# Rectfier.net
KiCad netlist of a schematic drawn in Altium Designer
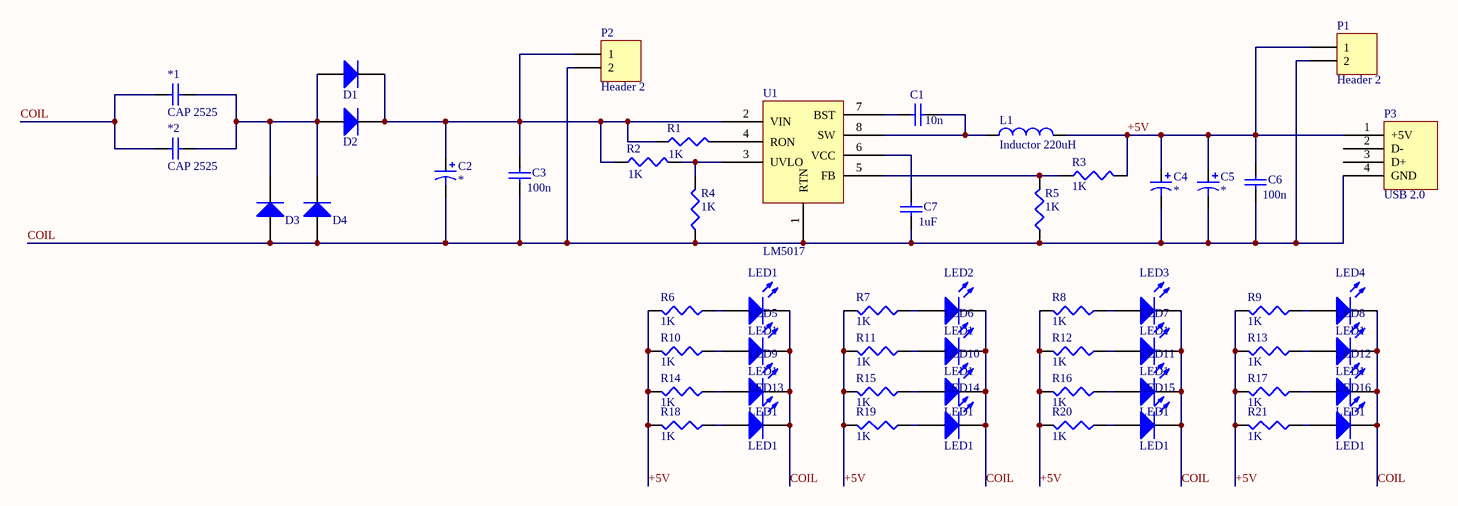
[diagram p0: Rectfier.SchDoc]

(export (version "E")
  (design (tool "Eeschema 10.0.6"))
  (components
    (comp (ref "*1")
      (value "CAP 2525")
      (footprint "CAP 2525")
      (libsource (lib "GaN_Schlib") (part "CAP 2525"))
    )
    (comp (ref "*2")
      (value "CAP 2525")
      (footprint "CAP 2525")
      (libsource (lib "GaN_Schlib") (part "CAP 2525"))
    )
    (comp (ref "C1")
      (value "10n")
      (footprint "0603 IPC Low Density")
      (description "Capacitor (Semiconductor SIM Model)")
      (fields (field (name "Comment") "Cap Semi") (field (name "PUBLISHER") "Altium Limited"))
      (libsource (lib "Miscellaneous Devices") (part "Cap Semi"))
    )
    (comp (ref "C2")
      (value "CAP SMD ELECT")
      (footprint "CAP 200uF")
      (fields (field (name "ALTIUM_VALUE") "*"))
      (libsource (lib "GaN_Schlib") (part "CAP SMD ELECT"))
    )
    (comp (ref "C3")
      (value "100n")
      (footprint "0805 IPC Low Density")
      (description "Capacitor (Semiconductor SIM Model)")
      (fields (field (name "Comment") "Cap Semi") (field (name "PUBLISHER") "Altium Limited"))
      (libsource (lib "Miscellaneous Devices") (part "Cap Semi"))
    )
    (comp (ref "C4")
      (value "CAP SMD ELECT")
      (footprint "CAP 47uF")
      (fields (field (name "ALTIUM_VALUE") "*"))
      (libsource (lib "GaN_Schlib") (part "CAP SMD ELECT"))
    )
    (comp (ref "C5")
      (value "CAP SMD ELECT")
      (footprint "CAP 47uF")
      (fields (field (name "ALTIUM_VALUE") "*"))
      (libsource (lib "GaN_Schlib") (part "CAP SMD ELECT"))
    )
    (comp (ref "C6")
      (value "100n")
      (footprint "1206 IPC Low Density")
      (description "Capacitor (Semiconductor SIM Model)")
      (fields (field (name "Comment") "Cap Semi") (field (name "PUBLISHER") "Altium Limited"))
      (libsource (lib "Miscellaneous Devices") (part "Cap Semi"))
    )
    (comp (ref "C7")
      (value "1uF")
      (footprint "0603 IPC Low Density")
      (description "Capacitor (Semiconductor SIM Model)")
      (fields (field (name "Comment") "Cap Semi") (field (name "PUBLISHER") "Altium Limited"))
      (libsource (lib "Miscellaneous Devices") (part "Cap Semi"))
    )
    (comp (ref "D1")
      (value "SiC Schottky Diode")
      (footprint "TO-263-2")
      (description "Cree Silicon Carbide Schottky Diode")
      (libsource (lib "GaN_Schlib") (part "SiC Schottky Diode"))
    )
    (comp (ref "D2")
      (value "SiC Schottky Diode")
      (footprint "QFN 3.3")
      (description "Cree Silicon Carbide Schottky Diode")
      (libsource (lib "GaN_Schlib") (part "SiC Schottky Diode"))
    )
    (comp (ref "D3")
      (value "SiC Schottky Diode")
      (footprint "QFN 3.3")
      (description "Cree Silicon Carbide Schottky Diode")
      (libsource (lib "GaN_Schlib") (part "SiC Schottky Diode"))
    )
    (comp (ref "D4")
      (value "SiC Schottky Diode")
      (footprint "TO-263-2")
      (description "Cree Silicon Carbide Schottky Diode")
      (libsource (lib "GaN_Schlib") (part "SiC Schottky Diode"))
    )
    (comp (ref "L1")
      (value "Inductor 220uH")
      (footprint "220u Indcutor small")
      (libsource (lib "GaN_Schlib") (part "Inductor 220uH"))
    )
    (comp (ref "LED1") (value "LED1") (footprint "LED 5MM") (libsource (lib "GaN_Schlib") (part "LED1")))
    (comp (ref "LED2") (value "LED1") (footprint "LED 5MM") (libsource (lib "GaN_Schlib") (part "LED1")))
    (comp (ref "LED3") (value "LED1") (footprint "LED 5MM") (libsource (lib "GaN_Schlib") (part "LED1")))
    (comp (ref "LED4") (value "LED1") (footprint "LED 5MM") (libsource (lib "GaN_Schlib") (part "LED1")))
    (comp (ref "LED5") (value "LED1") (footprint "LED 5MM") (libsource (lib "GaN_Schlib") (part "LED1")))
    (comp (ref "LED6") (value "LED1") (footprint "LED 5MM") (libsource (lib "GaN_Schlib") (part "LED1")))
    (comp (ref "LED7") (value "LED1") (footprint "LED 5MM") (libsource (lib "GaN_Schlib") (part "LED1")))
    (comp (ref "LED8") (value "LED1") (footprint "LED 5MM") (libsource (lib "GaN_Schlib") (part "LED1")))
    (comp (ref "LED9") (value "LED1") (footprint "LED 5MM") (libsource (lib "GaN_Schlib") (part "LED1")))
    (comp (ref "LED10") (value "LED1") (footprint "LED 5MM") (libsource (lib "GaN_Schlib") (part "LED1")))
    (comp (ref "LED11") (value "LED1") (footprint "LED 5MM") (libsource (lib "GaN_Schlib") (part "LED1")))
    (comp (ref "LED12") (value "LED1") (footprint "LED 5MM") (libsource (lib "GaN_Schlib") (part "LED1")))
    (comp (ref "LED13") (value "LED1") (footprint "LED 5MM") (libsource (lib "GaN_Schlib") (part "LED1")))
    (comp (ref "LED14") (value "LED1") (footprint "LED 5MM") (libsource (lib "GaN_Schlib") (part "LED1")))
    (comp (ref "LED15") (value "LED1") (footprint "LED 5MM") (libsource (lib "GaN_Schlib") (part "LED1")))
    (comp (ref "LED16") (value "LED1") (footprint "LED 5MM") (libsource (lib "GaN_Schlib") (part "LED1")))
    (comp (ref "P1")
      (value "Header 2")
      (footprint "HDR1X2")
      (description "Header, 2-Pin")
      (fields (field (name "PUBLISHER") "Altium Limited"))
      (libsource (lib "Miscellaneous Connectors") (part "Header 2"))
    )
    (comp (ref "P2")
      (value "Header 2")
      (footprint "HDR1X2")
      (description "Header, 2-Pin")
      (fields (field (name "PUBLISHER") "Altium Limited"))
      (libsource (lib "Miscellaneous Connectors") (part "Header 2"))
    )
    (comp (ref "P3") (value "USB 2.0") (footprint "USB 2.0") (libsource (lib "GaN_Schlib") (part "USB 2.0")))
    (comp (ref "R1")
      (value "1K")
      (footprint "RESISTOR 0603")
      (description "Resistor")
      (fields (field (name "Comment") "Res3") (field (name "PUBLISHER") "Altium Limited"))
      (libsource (lib "Miscellaneous Devices") (part "Res3"))
    )
    (comp (ref "R2")
      (value "1K")
      (footprint "RESISTOR 0603")
      (description "Resistor")
      (fields (field (name "Comment") "Res3") (field (name "PUBLISHER") "Altium Limited"))
      (libsource (lib "Miscellaneous Devices") (part "Res3"))
    )
    (comp (ref "R3")
      (value "1K")
      (footprint "RESISTOR 0603")
      (description "Resistor")
      (fields (field (name "Comment") "Res3") (field (name "PUBLISHER") "Altium Limited"))
      (libsource (lib "Miscellaneous Devices") (part "Res3"))
    )
    (comp (ref "R4")
      (value "1K")
      (footprint "RESISTOR 0603")
      (description "Resistor")
      (fields (field (name "Comment") "Res3") (field (name "PUBLISHER") "Altium Limited"))
      (libsource (lib "Miscellaneous Devices") (part "Res3"))
    )
    (comp (ref "R5")
      (value "1K")
      (footprint "RESISTOR 0603")
      (description "Resistor")
      (fields (field (name "Comment") "Res3") (field (name "PUBLISHER") "Altium Limited"))
      (libsource (lib "Miscellaneous Devices") (part "Res3"))
    )
    (comp (ref "R6")
      (value "1K")
      (footprint "RESISTOR 0603")
      (description "Resistor")
      (fields (field (name "Comment") "Res3") (field (name "PUBLISHER") "Altium Limited"))
      (libsource (lib "Miscellaneous Devices") (part "Res3"))
    )
    (comp (ref "R7")
      (value "1K")
      (footprint "RESISTOR 0603")
      (description "Resistor")
      (fields (field (name "Comment") "Res3") (field (name "PUBLISHER") "Altium Limited"))
      (libsource (lib "Miscellaneous Devices") (part "Res3"))
    )
    (comp (ref "R8")
      (value "1K")
      (footprint "RESISTOR 0603")
      (description "Resistor")
      (fields (field (name "Comment") "Res3") (field (name "PUBLISHER") "Altium Limited"))
      (libsource (lib "Miscellaneous Devices") (part "Res3"))
    )
    (comp (ref "R9")
      (value "1K")
      (footprint "RESISTOR 0603")
      (description "Resistor")
      (fields (field (name "Comment") "Res3") (field (name "PUBLISHER") "Altium Limited"))
      (libsource (lib "Miscellaneous Devices") (part "Res3"))
    )
    (comp (ref "R10")
      (value "1K")
      (footprint "RESISTOR 0603")
      (description "Resistor")
      (fields (field (name "Comment") "Res3") (field (name "PUBLISHER") "Altium Limited"))
      (libsource (lib "Miscellaneous Devices") (part "Res3"))
    )
    (comp (ref "R11")
      (value "1K")
      (footprint "RESISTOR 0603")
      (description "Resistor")
      (fields (field (name "Comment") "Res3") (field (name "PUBLISHER") "Altium Limited"))
      (libsource (lib "Miscellaneous Devices") (part "Res3"))
    )
    (comp (ref "R12")
      (value "1K")
      (footprint "RESISTOR 0603")
      (description "Resistor")
      (fields (field (name "Comment") "Res3") (field (name "PUBLISHER") "Altium Limited"))
      (libsource (lib "Miscellaneous Devices") (part "Res3"))
    )
    (comp (ref "R13")
      (value "1K")
      (footprint "RESISTOR 0603")
      (description "Resistor")
      (fields (field (name "Comment") "Res3") (field (name "PUBLISHER") "Altium Limited"))
      (libsource (lib "Miscellaneous Devices") (part "Res3"))
    )
    (comp (ref "R14")
      (value "1K")
      (footprint "RESISTOR 0603")
      (description "Resistor")
      (fields (field (name "Comment") "Res3") (field (name "PUBLISHER") "Altium Limited"))
      (libsource (lib "Miscellaneous Devices") (part "Res3"))
    )
    (comp (ref "R15")
      (value "1K")
      (footprint "RESISTOR 0603")
      (description "Resistor")
      (fields (field (name "Comment") "Res3") (field (name "PUBLISHER") "Altium Limited"))
      (libsource (lib "Miscellaneous Devices") (part "Res3"))
    )
    (comp (ref "R16")
      (value "1K")
      (footprint "RESISTOR 0603")
      (description "Resistor")
      (fields (field (name "Comment") "Res3") (field (name "PUBLISHER") "Altium Limited"))
      (libsource (lib "Miscellaneous Devices") (part "Res3"))
    )
    (comp (ref "R17")
      (value "1K")
      (footprint "RESISTOR 0603")
      (description "Resistor")
      (fields (field (name "Comment") "Res3") (field (name "PUBLISHER") "Altium Limited"))
      (libsource (lib "Miscellaneous Devices") (part "Res3"))
    )
    (comp (ref "R18")
      (value "1K")
      (footprint "RESISTOR 0603")
      (description "Resistor")
      (fields (field (name "Comment") "Res3") (field (name "PUBLISHER") "Altium Limited"))
      (libsource (lib "Miscellaneous Devices") (part "Res3"))
    )
    (comp (ref "R19")
      (value "1K")
      (footprint "RESISTOR 0603")
      (description "Resistor")
      (fields (field (name "Comment") "Res3") (field (name "PUBLISHER") "Altium Limited"))
      (libsource (lib "Miscellaneous Devices") (part "Res3"))
    )
    (comp (ref "R20")
      (value "1K")
      (footprint "RESISTOR 0603")
      (description "Resistor")
      (fields (field (name "Comment") "Res3") (field (name "PUBLISHER") "Altium Limited"))
      (libsource (lib "Miscellaneous Devices") (part "Res3"))
    )
    (comp (ref "R21")
      (value "1K")
      (footprint "RESISTOR 0603")
      (description "Resistor")
      (fields (field (name "Comment") "Res3") (field (name "PUBLISHER") "Altium Limited"))
      (libsource (lib "Miscellaneous Devices") (part "Res3"))
    )
    (comp (ref "U1")
      (value "LM5017")
      (footprint "SOIC8_THERMAL")
      (libsource (lib "GaN_Schlib") (part "LM5017"))
    )
  )
  (nets
    (net (code "1") (name "/+5V") (class "Default")
      (node (ref "C4") (pin "A") (pinfunction "A_A") (pintype "passive"))
      (node (ref "C5") (pin "A") (pinfunction "A_A") (pintype "passive"))
      (node (ref "C6") (pin "2") (pinfunction "2_2") (pintype "passive"))
      (node (ref "L1") (pin "2") (pinfunction "2_2") (pintype "passive"))
      (node (ref "P1") (pin "1") (pinfunction "1_1") (pintype "passive"))
      (node (ref "P3") (pin "1") (pinfunction "+5V_1") (pintype "passive"))
      (node (ref "R10") (pin "2") (pinfunction "2_2") (pintype "passive"))
      (node (ref "R11") (pin "2") (pinfunction "2_2") (pintype "passive"))
      (node (ref "R12") (pin "2") (pinfunction "2_2") (pintype "passive"))
      (node (ref "R13") (pin "2") (pinfunction "2_2") (pintype "passive"))
      (node (ref "R14") (pin "2") (pinfunction "2_2") (pintype "passive"))
      (node (ref "R15") (pin "2") (pinfunction "2_2") (pintype "passive"))
      (node (ref "R16") (pin "2") (pinfunction "2_2") (pintype "passive"))
      (node (ref "R17") (pin "2") (pinfunction "2_2") (pintype "passive"))
      (node (ref "R18") (pin "2") (pinfunction "2_2") (pintype "passive"))
      (node (ref "R19") (pin "2") (pinfunction "2_2") (pintype "passive"))
      (node (ref "R20") (pin "2") (pinfunction "2_2") (pintype "passive"))
      (node (ref "R21") (pin "2") (pinfunction "2_2") (pintype "passive"))
      (node (ref "R3") (pin "2") (pinfunction "2_2") (pintype "passive"))
      (node (ref "R6") (pin "2") (pinfunction "2_2") (pintype "passive"))
      (node (ref "R7") (pin "2") (pinfunction "2_2") (pintype "passive"))
      (node (ref "R8") (pin "2") (pinfunction "2_2") (pintype "passive"))
      (node (ref "R9") (pin "2") (pinfunction "2_2") (pintype "passive"))
    )
    (net (code "2") (name "/COIL") (class "Default")
      (node (ref "*1") (pin "1") (pinfunction "1_1") (pintype "passive"))
      (node (ref "*2") (pin "1") (pinfunction "1_1") (pintype "passive"))
      (node (ref "C2") (pin "C") (pinfunction "C_C") (pintype "passive"))
      (node (ref "C3") (pin "1") (pinfunction "1_1") (pintype "passive"))
      (node (ref "C4") (pin "C") (pinfunction "C_C") (pintype "passive"))
      (node (ref "C5") (pin "C") (pinfunction "C_C") (pintype "passive"))
      (node (ref "C6") (pin "1") (pinfunction "1_1") (pintype "passive"))
      (node (ref "C7") (pin "1") (pinfunction "1_1") (pintype "passive"))
      (node (ref "D3") (pin "A") (pinfunction "A_A") (pintype "passive"))
      (node (ref "D4") (pin "A") (pinfunction "A_A") (pintype "passive"))
      (node (ref "LED1") (pin "K") (pinfunction "K_K") (pintype "passive"))
      (node (ref "LED10") (pin "K") (pinfunction "K_K") (pintype "passive"))
      (node (ref "LED11") (pin "K") (pinfunction "K_K") (pintype "passive"))
      (node (ref "LED12") (pin "K") (pinfunction "K_K") (pintype "passive"))
      (node (ref "LED13") (pin "K") (pinfunction "K_K") (pintype "passive"))
      (node (ref "LED14") (pin "K") (pinfunction "K_K") (pintype "passive"))
      (node (ref "LED15") (pin "K") (pinfunction "K_K") (pintype "passive"))
      (node (ref "LED16") (pin "K") (pinfunction "K_K") (pintype "passive"))
      (node (ref "LED2") (pin "K") (pinfunction "K_K") (pintype "passive"))
      (node (ref "LED3") (pin "K") (pinfunction "K_K") (pintype "passive"))
      (node (ref "LED4") (pin "K") (pinfunction "K_K") (pintype "passive"))
      (node (ref "LED5") (pin "K") (pinfunction "K_K") (pintype "passive"))
      (node (ref "LED6") (pin "K") (pinfunction "K_K") (pintype "passive"))
      (node (ref "LED7") (pin "K") (pinfunction "K_K") (pintype "passive"))
      (node (ref "LED8") (pin "K") (pinfunction "K_K") (pintype "passive"))
      (node (ref "LED9") (pin "K") (pinfunction "K_K") (pintype "passive"))
      (node (ref "P1") (pin "2") (pinfunction "2_2") (pintype "passive"))
      (node (ref "P2") (pin "2") (pinfunction "2_2") (pintype "passive"))
      (node (ref "P3") (pin "4") (pinfunction "GND_4") (pintype "passive"))
      (node (ref "R4") (pin "1") (pinfunction "1_1") (pintype "passive"))
      (node (ref "R5") (pin "1") (pinfunction "1_1") (pintype "passive"))
      (node (ref "U1") (pin "1") (pinfunction "RTN_1") (pintype "passive"))
    )
    (net (code "3") (name "Net-(*1-Pad2)") (class "Default")
      (node (ref "*1") (pin "2") (pinfunction "2_2") (pintype "passive"))
      (node (ref "*2") (pin "2") (pinfunction "2_2") (pintype "passive"))
      (node (ref "D1") (pin "A") (pinfunction "A_A") (pintype "passive"))
      (node (ref "D2") (pin "A") (pinfunction "A_A") (pintype "passive"))
      (node (ref "D3") (pin "C") (pinfunction "C_C") (pintype "passive"))
      (node (ref "D4") (pin "C") (pinfunction "C_C") (pintype "passive"))
    )
    (net (code "4") (name "Net-(LED1-PadA)") (class "Default")
      (node (ref "LED1") (pin "A") (pinfunction "A_A") (pintype "passive"))
      (node (ref "R6") (pin "1") (pinfunction "1_1") (pintype "passive"))
    )
    (net (code "5") (name "Net-(LED2-PadA)") (class "Default")
      (node (ref "LED2") (pin "A") (pinfunction "A_A") (pintype "passive"))
      (node (ref "R7") (pin "1") (pinfunction "1_1") (pintype "passive"))
    )
    (net (code "6") (name "Net-(LED3-PadA)") (class "Default")
      (node (ref "LED3") (pin "A") (pinfunction "A_A") (pintype "passive"))
      (node (ref "R8") (pin "1") (pinfunction "1_1") (pintype "passive"))
    )
    (net (code "7") (name "Net-(LED4-PadA)") (class "Default")
      (node (ref "LED4") (pin "A") (pinfunction "A_A") (pintype "passive"))
      (node (ref "R9") (pin "1") (pinfunction "1_1") (pintype "passive"))
    )
    (net (code "8") (name "Net-(LED5-PadA)") (class "Default")
      (node (ref "LED5") (pin "A") (pinfunction "A_A") (pintype "passive"))
      (node (ref "R10") (pin "1") (pinfunction "1_1") (pintype "passive"))
    )
    (net (code "9") (name "Net-(LED6-PadA)") (class "Default")
      (node (ref "LED6") (pin "A") (pinfunction "A_A") (pintype "passive"))
      (node (ref "R11") (pin "1") (pinfunction "1_1") (pintype "passive"))
    )
    (net (code "10") (name "Net-(LED7-PadA)") (class "Default")
      (node (ref "LED7") (pin "A") (pinfunction "A_A") (pintype "passive"))
      (node (ref "R12") (pin "1") (pinfunction "1_1") (pintype "passive"))
    )
    (net (code "11") (name "Net-(LED8-PadA)") (class "Default")
      (node (ref "LED8") (pin "A") (pinfunction "A_A") (pintype "passive"))
      (node (ref "R13") (pin "1") (pinfunction "1_1") (pintype "passive"))
    )
    (net (code "12") (name "Net-(LED9-PadA)") (class "Default")
      (node (ref "LED9") (pin "A") (pinfunction "A_A") (pintype "passive"))
      (node (ref "R14") (pin "1") (pinfunction "1_1") (pintype "passive"))
    )
    (net (code "13") (name "Net-(LED10-PadA)") (class "Default")
      (node (ref "LED10") (pin "A") (pinfunction "A_A") (pintype "passive"))
      (node (ref "R15") (pin "1") (pinfunction "1_1") (pintype "passive"))
    )
    (net (code "14") (name "Net-(LED11-PadA)") (class "Default")
      (node (ref "LED11") (pin "A") (pinfunction "A_A") (pintype "passive"))
      (node (ref "R16") (pin "1") (pinfunction "1_1") (pintype "passive"))
    )
    (net (code "15") (name "Net-(LED12-PadA)") (class "Default")
      (node (ref "LED12") (pin "A") (pinfunction "A_A") (pintype "passive"))
      (node (ref "R17") (pin "1") (pinfunction "1_1") (pintype "passive"))
    )
    (net (code "16") (name "Net-(LED13-PadA)") (class "Default")
      (node (ref "LED13") (pin "A") (pinfunction "A_A") (pintype "passive"))
      (node (ref "R18") (pin "1") (pinfunction "1_1") (pintype "passive"))
    )
    (net (code "17") (name "Net-(LED14-PadA)") (class "Default")
      (node (ref "LED14") (pin "A") (pinfunction "A_A") (pintype "passive"))
      (node (ref "R19") (pin "1") (pinfunction "1_1") (pintype "passive"))
    )
    (net (code "18") (name "Net-(LED15-PadA)") (class "Default")
      (node (ref "LED15") (pin "A") (pinfunction "A_A") (pintype "passive"))
      (node (ref "R20") (pin "1") (pinfunction "1_1") (pintype "passive"))
    )
    (net (code "19") (name "Net-(LED16-PadA)") (class "Default")
      (node (ref "LED16") (pin "A") (pinfunction "A_A") (pintype "passive"))
      (node (ref "R21") (pin "1") (pinfunction "1_1") (pintype "passive"))
    )
    (net (code "20") (name "Net-(U1-BST)") (class "Default")
      (node (ref "C1") (pin "1") (pinfunction "1_1") (pintype "passive"))
      (node (ref "U1") (pin "7") (pinfunction "BST_7") (pintype "passive"))
    )
    (net (code "21") (name "Net-(U1-FB)") (class "Default")
      (node (ref "R3") (pin "1") (pinfunction "1_1") (pintype "passive"))
      (node (ref "R5") (pin "2") (pinfunction "2_2") (pintype "passive"))
      (node (ref "U1") (pin "5") (pinfunction "FB_5") (pintype "passive"))
    )
    (net (code "22") (name "Net-(U1-RON)") (class "Default")
      (node (ref "R1") (pin "2") (pinfunction "2_2") (pintype "passive"))
      (node (ref "U1") (pin "4") (pinfunction "RON_4") (pintype "passive"))
    )
    (net (code "23") (name "Net-(U1-SW)") (class "Default")
      (node (ref "C1") (pin "2") (pinfunction "2_2") (pintype "passive"))
      (node (ref "L1") (pin "1") (pinfunction "1_1") (pintype "passive"))
      (node (ref "U1") (pin "8") (pinfunction "SW_8") (pintype "passive"))
    )
    (net (code "24") (name "Net-(U1-UVLO)") (class "Default")
      (node (ref "R2") (pin "2") (pinfunction "2_2") (pintype "passive"))
      (node (ref "R4") (pin "2") (pinfunction "2_2") (pintype "passive"))
      (node (ref "U1") (pin "3") (pinfunction "UVLO_3") (pintype "passive"))
    )
    (net (code "25") (name "Net-(U1-VCC)") (class "Default")
      (node (ref "C7") (pin "2") (pinfunction "2_2") (pintype "passive"))
      (node (ref "U1") (pin "6") (pinfunction "VCC_6") (pintype "passive"))
    )
    (net (code "26") (name "Net-(U1-VIN)") (class "Default")
      (node (ref "C2") (pin "A") (pinfunction "A_A") (pintype "passive"))
      (node (ref "C3") (pin "2") (pinfunction "2_2") (pintype "passive"))
      (node (ref "D1") (pin "C") (pinfunction "C_C") (pintype "passive"))
      (node (ref "D2") (pin "C") (pinfunction "C_C") (pintype "passive"))
      (node (ref "P2") (pin "1") (pinfunction "1_1") (pintype "passive"))
      (node (ref "R1") (pin "1") (pinfunction "1_1") (pintype "passive"))
      (node (ref "R2") (pin "1") (pinfunction "1_1") (pintype "passive"))
      (node (ref "U1") (pin "2") (pinfunction "VIN_2") (pintype "passive"))
    )
    (net (code "27") (name "unconnected-(P3-D+-Pad3)") (class "Default")
      (node (ref "P3") (pin "3") (pinfunction "D+_3") (pintype "passive"))
    )
    (net (code "28") (name "unconnected-(P3-D--Pad2)") (class "Default")
      (node (ref "P3") (pin "2") (pinfunction "D-_2") (pintype "passive"))
    )
  )
)
